# pushi.net
KiCad netlist of a schematic drawn in EAGLE
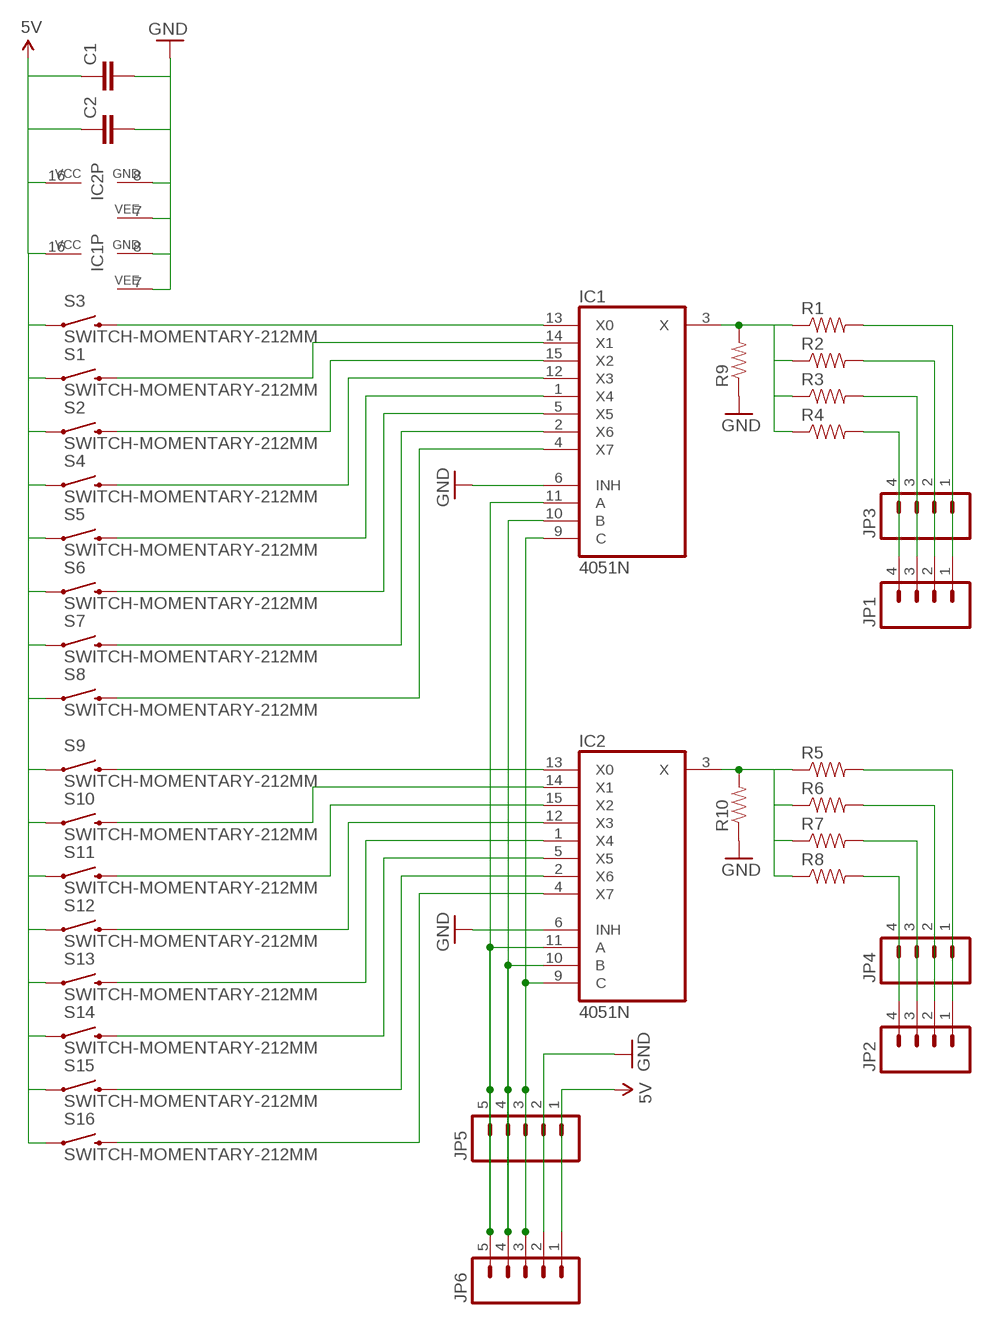
[diagram p0: schematic, sheet 1]

(export (version "E")
  (design (tool "Eeschema 10.0.6"))
  (components
    (comp (ref "C1")
      (value "CAPPTH")
      (footprint "eagle-import:CAP-PTH-SMALL")
      (libsource (lib "eagle-import") (part "CAPPTH"))
    )
    (comp (ref "C2")
      (value "CAPPTH")
      (footprint "eagle-import:CAP-PTH-SMALL")
      (libsource (lib "eagle-import") (part "CAPPTH"))
    )
    (comp (ref "IC1")
      (value "4051N")
      (footprint "eagle-import:DIL16")
      (libsource (lib "eagle-import") (part "4051N"))
    )
    (comp (ref "IC2")
      (value "4051N")
      (footprint "eagle-import:DIL16")
      (libsource (lib "eagle-import") (part "4051N"))
    )
    (comp (ref "JP1")
      (value "M04PTH")
      (footprint "eagle-import:1X04")
      (libsource (lib "eagle-import") (part "M04PTH"))
    )
    (comp (ref "JP2")
      (value "M04PTH")
      (footprint "eagle-import:1X04")
      (libsource (lib "eagle-import") (part "M04PTH"))
    )
    (comp (ref "JP3")
      (value "M04PTH")
      (footprint "eagle-import:1X04")
      (libsource (lib "eagle-import") (part "M04PTH"))
    )
    (comp (ref "JP4")
      (value "M04PTH")
      (footprint "eagle-import:1X04")
      (libsource (lib "eagle-import") (part "M04PTH"))
    )
    (comp (ref "JP5")
      (value "M05PTH")
      (footprint "eagle-import:1X05")
      (libsource (lib "eagle-import") (part "M05PTH"))
    )
    (comp (ref "JP6")
      (value "M05PTH")
      (footprint "eagle-import:1X05")
      (libsource (lib "eagle-import") (part "M05PTH"))
    )
    (comp (ref "R1")
      (value "RESISTORAXIAL-0.3")
      (footprint "eagle-import:AXIAL-0.3")
      (libsource (lib "eagle-import") (part "RESISTORAXIAL-0.3"))
    )
    (comp (ref "R2")
      (value "RESISTORAXIAL-0.3")
      (footprint "eagle-import:AXIAL-0.3")
      (libsource (lib "eagle-import") (part "RESISTORAXIAL-0.3"))
    )
    (comp (ref "R3")
      (value "RESISTORAXIAL-0.3")
      (footprint "eagle-import:AXIAL-0.3")
      (libsource (lib "eagle-import") (part "RESISTORAXIAL-0.3"))
    )
    (comp (ref "R4")
      (value "RESISTORAXIAL-0.3")
      (footprint "eagle-import:AXIAL-0.3")
      (libsource (lib "eagle-import") (part "RESISTORAXIAL-0.3"))
    )
    (comp (ref "R5")
      (value "RESISTORAXIAL-0.3")
      (footprint "eagle-import:AXIAL-0.3")
      (libsource (lib "eagle-import") (part "RESISTORAXIAL-0.3"))
    )
    (comp (ref "R6")
      (value "RESISTORAXIAL-0.3")
      (footprint "eagle-import:AXIAL-0.3")
      (libsource (lib "eagle-import") (part "RESISTORAXIAL-0.3"))
    )
    (comp (ref "R7")
      (value "RESISTORAXIAL-0.3")
      (footprint "eagle-import:AXIAL-0.3")
      (libsource (lib "eagle-import") (part "RESISTORAXIAL-0.3"))
    )
    (comp (ref "R8")
      (value "RESISTORAXIAL-0.3")
      (footprint "eagle-import:AXIAL-0.3")
      (libsource (lib "eagle-import") (part "RESISTORAXIAL-0.3"))
    )
    (comp (ref "R9")
      (value "RESISTORAXIAL-0.3")
      (footprint "eagle-import:AXIAL-0.3")
      (libsource (lib "eagle-import") (part "RESISTORAXIAL-0.3"))
    )
    (comp (ref "R10")
      (value "RESISTORAXIAL-0.3")
      (footprint "eagle-import:AXIAL-0.3")
      (libsource (lib "eagle-import") (part "RESISTORAXIAL-0.3"))
    )
    (comp (ref "S1")
      (value "SWITCH-MOMENTARY-212MM")
      (footprint "eagle-import:TACTILE-PTH-12MM")
      (libsource (lib "eagle-import") (part "SWITCH-MOMENTARY-212MM"))
    )
    (comp (ref "S2")
      (value "SWITCH-MOMENTARY-212MM")
      (footprint "eagle-import:TACTILE-PTH-12MM")
      (libsource (lib "eagle-import") (part "SWITCH-MOMENTARY-212MM"))
    )
    (comp (ref "S3")
      (value "SWITCH-MOMENTARY-212MM")
      (footprint "eagle-import:TACTILE-PTH-12MM")
      (libsource (lib "eagle-import") (part "SWITCH-MOMENTARY-212MM"))
    )
    (comp (ref "S4")
      (value "SWITCH-MOMENTARY-212MM")
      (footprint "eagle-import:TACTILE-PTH-12MM")
      (libsource (lib "eagle-import") (part "SWITCH-MOMENTARY-212MM"))
    )
    (comp (ref "S5")
      (value "SWITCH-MOMENTARY-212MM")
      (footprint "eagle-import:TACTILE-PTH-12MM")
      (libsource (lib "eagle-import") (part "SWITCH-MOMENTARY-212MM"))
    )
    (comp (ref "S6")
      (value "SWITCH-MOMENTARY-212MM")
      (footprint "eagle-import:TACTILE-PTH-12MM")
      (libsource (lib "eagle-import") (part "SWITCH-MOMENTARY-212MM"))
    )
    (comp (ref "S7")
      (value "SWITCH-MOMENTARY-212MM")
      (footprint "eagle-import:TACTILE-PTH-12MM")
      (libsource (lib "eagle-import") (part "SWITCH-MOMENTARY-212MM"))
    )
    (comp (ref "S8")
      (value "SWITCH-MOMENTARY-212MM")
      (footprint "eagle-import:TACTILE-PTH-12MM")
      (libsource (lib "eagle-import") (part "SWITCH-MOMENTARY-212MM"))
    )
    (comp (ref "S9")
      (value "SWITCH-MOMENTARY-212MM")
      (footprint "eagle-import:TACTILE-PTH-12MM")
      (libsource (lib "eagle-import") (part "SWITCH-MOMENTARY-212MM"))
    )
    (comp (ref "S10")
      (value "SWITCH-MOMENTARY-212MM")
      (footprint "eagle-import:TACTILE-PTH-12MM")
      (libsource (lib "eagle-import") (part "SWITCH-MOMENTARY-212MM"))
    )
    (comp (ref "S11")
      (value "SWITCH-MOMENTARY-212MM")
      (footprint "eagle-import:TACTILE-PTH-12MM")
      (libsource (lib "eagle-import") (part "SWITCH-MOMENTARY-212MM"))
    )
    (comp (ref "S12")
      (value "SWITCH-MOMENTARY-212MM")
      (footprint "eagle-import:TACTILE-PTH-12MM")
      (libsource (lib "eagle-import") (part "SWITCH-MOMENTARY-212MM"))
    )
    (comp (ref "S13")
      (value "SWITCH-MOMENTARY-212MM")
      (footprint "eagle-import:TACTILE-PTH-12MM")
      (libsource (lib "eagle-import") (part "SWITCH-MOMENTARY-212MM"))
    )
    (comp (ref "S14")
      (value "SWITCH-MOMENTARY-212MM")
      (footprint "eagle-import:TACTILE-PTH-12MM")
      (libsource (lib "eagle-import") (part "SWITCH-MOMENTARY-212MM"))
    )
    (comp (ref "S15")
      (value "SWITCH-MOMENTARY-212MM")
      (footprint "eagle-import:TACTILE-PTH-12MM")
      (libsource (lib "eagle-import") (part "SWITCH-MOMENTARY-212MM"))
    )
    (comp (ref "S16")
      (value "SWITCH-MOMENTARY-212MM")
      (footprint "eagle-import:TACTILE-PTH-12MM")
      (libsource (lib "eagle-import") (part "SWITCH-MOMENTARY-212MM"))
    )
  )
  (nets
    (net (code "1") (name "5V") (class "Default")
      (node (ref "C1") (pin "1") (pinfunction "1_1") (pintype "passive"))
      (node (ref "C2") (pin "1") (pinfunction "1_1") (pintype "passive"))
      (node (ref "IC1") (pin "16") (pinfunction "VCC_16") (pintype "power_in"))
      (node (ref "IC2") (pin "16") (pinfunction "VCC_16") (pintype "power_in"))
      (node (ref "JP5") (pin "1") (pinfunction "1_1") (pintype "passive"))
      (node (ref "JP6") (pin "1") (pinfunction "1_1") (pintype "passive"))
      (node (ref "S1") (pin "1") (pinfunction "1_1") (pintype "passive"))
      (node (ref "S10") (pin "1") (pinfunction "1_1") (pintype "passive"))
      (node (ref "S11") (pin "1") (pinfunction "1_1") (pintype "passive"))
      (node (ref "S12") (pin "1") (pinfunction "1_1") (pintype "passive"))
      (node (ref "S13") (pin "1") (pinfunction "1_1") (pintype "passive"))
      (node (ref "S14") (pin "1") (pinfunction "1_1") (pintype "passive"))
      (node (ref "S15") (pin "1") (pinfunction "1_1") (pintype "passive"))
      (node (ref "S16") (pin "1") (pinfunction "1_1") (pintype "passive"))
      (node (ref "S2") (pin "1") (pinfunction "1_1") (pintype "passive"))
      (node (ref "S3") (pin "1") (pinfunction "1_1") (pintype "passive"))
      (node (ref "S4") (pin "1") (pinfunction "1_1") (pintype "passive"))
      (node (ref "S5") (pin "1") (pinfunction "1_1") (pintype "passive"))
      (node (ref "S6") (pin "1") (pinfunction "1_1") (pintype "passive"))
      (node (ref "S7") (pin "1") (pinfunction "1_1") (pintype "passive"))
      (node (ref "S8") (pin "1") (pinfunction "1_1") (pintype "passive"))
      (node (ref "S9") (pin "1") (pinfunction "1_1") (pintype "passive"))
    )
    (net (code "2") (name "GND") (class "Default")
      (node (ref "C1") (pin "2") (pinfunction "2_2") (pintype "passive"))
      (node (ref "C2") (pin "2") (pinfunction "2_2") (pintype "passive"))
      (node (ref "IC1") (pin "6") (pinfunction "INH_6") (pintype "input"))
      (node (ref "IC1") (pin "7") (pinfunction "VEE_7") (pintype "power_in"))
      (node (ref "IC1") (pin "8") (pinfunction "GND_8") (pintype "power_in"))
      (node (ref "IC2") (pin "6") (pinfunction "INH_6") (pintype "input"))
      (node (ref "IC2") (pin "7") (pinfunction "VEE_7") (pintype "power_in"))
      (node (ref "IC2") (pin "8") (pinfunction "GND_8") (pintype "power_in"))
      (node (ref "JP5") (pin "2") (pinfunction "2_2") (pintype "passive"))
      (node (ref "JP6") (pin "2") (pinfunction "2_2") (pintype "passive"))
      (node (ref "R10") (pin "P$1") (pinfunction "1_P$1") (pintype "passive"))
      (node (ref "R9") (pin "P$1") (pinfunction "1_P$1") (pintype "passive"))
    )
    (net (code "3") (name "Net-(IC1A-A)") (class "Default")
      (node (ref "IC1") (pin "11") (pinfunction "A_11") (pintype "input"))
      (node (ref "IC2") (pin "11") (pinfunction "A_11") (pintype "input"))
      (node (ref "JP5") (pin "5") (pinfunction "5_5") (pintype "passive"))
      (node (ref "JP6") (pin "5") (pinfunction "5_5") (pintype "passive"))
    )
    (net (code "4") (name "Net-(IC1A-B)") (class "Default")
      (node (ref "IC1") (pin "10") (pinfunction "B_10") (pintype "input"))
      (node (ref "IC2") (pin "10") (pinfunction "B_10") (pintype "input"))
      (node (ref "JP5") (pin "4") (pinfunction "4_4") (pintype "passive"))
      (node (ref "JP6") (pin "4") (pinfunction "4_4") (pintype "passive"))
    )
    (net (code "5") (name "Net-(IC1A-C)") (class "Default")
      (node (ref "IC1") (pin "9") (pinfunction "C_9") (pintype "input"))
      (node (ref "IC2") (pin "9") (pinfunction "C_9") (pintype "input"))
      (node (ref "JP5") (pin "3") (pinfunction "3_3") (pintype "passive"))
      (node (ref "JP6") (pin "3") (pinfunction "3_3") (pintype "passive"))
    )
    (net (code "6") (name "Net-(IC1A-X)") (class "Default")
      (node (ref "IC1") (pin "3") (pinfunction "X_3") (pintype "bidirectional"))
      (node (ref "R1") (pin "P$1") (pinfunction "1_P$1") (pintype "passive"))
      (node (ref "R2") (pin "P$1") (pinfunction "1_P$1") (pintype "passive"))
      (node (ref "R3") (pin "P$1") (pinfunction "1_P$1") (pintype "passive"))
      (node (ref "R4") (pin "P$1") (pinfunction "1_P$1") (pintype "passive"))
      (node (ref "R9") (pin "P$2") (pinfunction "2_P$2") (pintype "passive"))
    )
    (net (code "7") (name "Net-(IC1A-X0)") (class "Default")
      (node (ref "IC1") (pin "13") (pinfunction "X0_13") (pintype "bidirectional"))
      (node (ref "S3") (pin "3") (pinfunction "2_3") (pintype "passive"))
    )
    (net (code "8") (name "Net-(IC1A-X1)") (class "Default")
      (node (ref "IC1") (pin "14") (pinfunction "X1_14") (pintype "bidirectional"))
      (node (ref "S1") (pin "3") (pinfunction "2_3") (pintype "passive"))
    )
    (net (code "9") (name "Net-(IC1A-X2)") (class "Default")
      (node (ref "IC1") (pin "15") (pinfunction "X2_15") (pintype "bidirectional"))
      (node (ref "S2") (pin "3") (pinfunction "2_3") (pintype "passive"))
    )
    (net (code "10") (name "Net-(IC1A-X3)") (class "Default")
      (node (ref "IC1") (pin "12") (pinfunction "X3_12") (pintype "bidirectional"))
      (node (ref "S4") (pin "3") (pinfunction "2_3") (pintype "passive"))
    )
    (net (code "11") (name "Net-(IC1A-X4)") (class "Default")
      (node (ref "IC1") (pin "1") (pinfunction "X4_1") (pintype "bidirectional"))
      (node (ref "S5") (pin "3") (pinfunction "2_3") (pintype "passive"))
    )
    (net (code "12") (name "Net-(IC1A-X5)") (class "Default")
      (node (ref "IC1") (pin "5") (pinfunction "X5_5") (pintype "bidirectional"))
      (node (ref "S6") (pin "3") (pinfunction "2_3") (pintype "passive"))
    )
    (net (code "13") (name "Net-(IC1A-X6)") (class "Default")
      (node (ref "IC1") (pin "2") (pinfunction "X6_2") (pintype "bidirectional"))
      (node (ref "S7") (pin "3") (pinfunction "2_3") (pintype "passive"))
    )
    (net (code "14") (name "Net-(IC1A-X7)") (class "Default")
      (node (ref "IC1") (pin "4") (pinfunction "X7_4") (pintype "bidirectional"))
      (node (ref "S8") (pin "3") (pinfunction "2_3") (pintype "passive"))
    )
    (net (code "15") (name "Net-(IC2A-X)") (class "Default")
      (node (ref "IC2") (pin "3") (pinfunction "X_3") (pintype "bidirectional"))
      (node (ref "R10") (pin "P$2") (pinfunction "2_P$2") (pintype "passive"))
      (node (ref "R5") (pin "P$1") (pinfunction "1_P$1") (pintype "passive"))
      (node (ref "R6") (pin "P$1") (pinfunction "1_P$1") (pintype "passive"))
      (node (ref "R7") (pin "P$1") (pinfunction "1_P$1") (pintype "passive"))
      (node (ref "R8") (pin "P$1") (pinfunction "1_P$1") (pintype "passive"))
    )
    (net (code "16") (name "Net-(IC2A-X0)") (class "Default")
      (node (ref "IC2") (pin "13") (pinfunction "X0_13") (pintype "bidirectional"))
      (node (ref "S9") (pin "3") (pinfunction "2_3") (pintype "passive"))
    )
    (net (code "17") (name "Net-(IC2A-X1)") (class "Default")
      (node (ref "IC2") (pin "14") (pinfunction "X1_14") (pintype "bidirectional"))
      (node (ref "S10") (pin "3") (pinfunction "2_3") (pintype "passive"))
    )
    (net (code "18") (name "Net-(IC2A-X2)") (class "Default")
      (node (ref "IC2") (pin "15") (pinfunction "X2_15") (pintype "bidirectional"))
      (node (ref "S11") (pin "3") (pinfunction "2_3") (pintype "passive"))
    )
    (net (code "19") (name "Net-(IC2A-X3)") (class "Default")
      (node (ref "IC2") (pin "12") (pinfunction "X3_12") (pintype "bidirectional"))
      (node (ref "S12") (pin "3") (pinfunction "2_3") (pintype "passive"))
    )
    (net (code "20") (name "Net-(IC2A-X4)") (class "Default")
      (node (ref "IC2") (pin "1") (pinfunction "X4_1") (pintype "bidirectional"))
      (node (ref "S13") (pin "3") (pinfunction "2_3") (pintype "passive"))
    )
    (net (code "21") (name "Net-(IC2A-X5)") (class "Default")
      (node (ref "IC2") (pin "5") (pinfunction "X5_5") (pintype "bidirectional"))
      (node (ref "S14") (pin "3") (pinfunction "2_3") (pintype "passive"))
    )
    (net (code "22") (name "Net-(IC2A-X6)") (class "Default")
      (node (ref "IC2") (pin "2") (pinfunction "X6_2") (pintype "bidirectional"))
      (node (ref "S15") (pin "3") (pinfunction "2_3") (pintype "passive"))
    )
    (net (code "23") (name "Net-(IC2A-X7)") (class "Default")
      (node (ref "IC2") (pin "4") (pinfunction "X7_4") (pintype "bidirectional"))
      (node (ref "S16") (pin "3") (pinfunction "2_3") (pintype "passive"))
    )
    (net (code "24") (name "Net-(R1-2)") (class "Default")
      (node (ref "JP1") (pin "1") (pinfunction "1_1") (pintype "passive"))
      (node (ref "JP3") (pin "1") (pinfunction "1_1") (pintype "passive"))
      (node (ref "R1") (pin "P$2") (pinfunction "2_P$2") (pintype "passive"))
    )
    (net (code "25") (name "Net-(R2-2)") (class "Default")
      (node (ref "JP1") (pin "2") (pinfunction "2_2") (pintype "passive"))
      (node (ref "JP3") (pin "2") (pinfunction "2_2") (pintype "passive"))
      (node (ref "R2") (pin "P$2") (pinfunction "2_P$2") (pintype "passive"))
    )
    (net (code "26") (name "Net-(R3-2)") (class "Default")
      (node (ref "JP1") (pin "3") (pinfunction "3_3") (pintype "passive"))
      (node (ref "JP3") (pin "3") (pinfunction "3_3") (pintype "passive"))
      (node (ref "R3") (pin "P$2") (pinfunction "2_P$2") (pintype "passive"))
    )
    (net (code "27") (name "Net-(R4-2)") (class "Default")
      (node (ref "JP1") (pin "4") (pinfunction "4_4") (pintype "passive"))
      (node (ref "JP3") (pin "4") (pinfunction "4_4") (pintype "passive"))
      (node (ref "R4") (pin "P$2") (pinfunction "2_P$2") (pintype "passive"))
    )
    (net (code "28") (name "Net-(R5-2)") (class "Default")
      (node (ref "JP2") (pin "1") (pinfunction "1_1") (pintype "passive"))
      (node (ref "JP4") (pin "1") (pinfunction "1_1") (pintype "passive"))
      (node (ref "R5") (pin "P$2") (pinfunction "2_P$2") (pintype "passive"))
    )
    (net (code "29") (name "Net-(R6-2)") (class "Default")
      (node (ref "JP2") (pin "2") (pinfunction "2_2") (pintype "passive"))
      (node (ref "JP4") (pin "2") (pinfunction "2_2") (pintype "passive"))
      (node (ref "R6") (pin "P$2") (pinfunction "2_P$2") (pintype "passive"))
    )
    (net (code "30") (name "Net-(R7-2)") (class "Default")
      (node (ref "JP2") (pin "3") (pinfunction "3_3") (pintype "passive"))
      (node (ref "JP4") (pin "3") (pinfunction "3_3") (pintype "passive"))
      (node (ref "R7") (pin "P$2") (pinfunction "2_P$2") (pintype "passive"))
    )
    (net (code "31") (name "Net-(R8-2)") (class "Default")
      (node (ref "JP2") (pin "4") (pinfunction "4_4") (pintype "passive"))
      (node (ref "JP4") (pin "4") (pinfunction "4_4") (pintype "passive"))
      (node (ref "R8") (pin "P$2") (pinfunction "2_P$2") (pintype "passive"))
    )
  )
)
